# interstage_A2v2.net
KiCad netlist of a schematic drawn in EAGLE
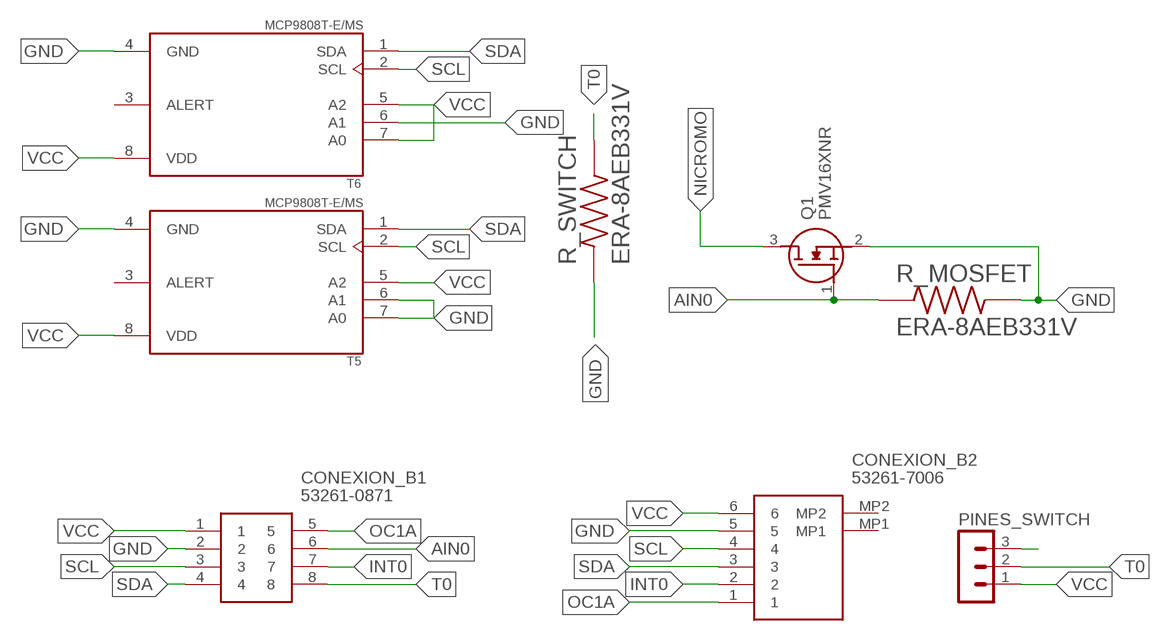
[diagram p0: schematic, sheet 1]

(export (version "E")
  (design (tool "Eeschema 10.0.6"))
  (components
    (comp (ref "CONEXION_B1")
      (value "53261-0871")
      (footprint "eagle-import:53261-0871")
      (fields (field (name "MOUSER_PART_NUMBER") "538-53261-0871"))
      (libsource (lib "eagle-import") (part "53261-0871"))
    )
    (comp (ref "CONEXION_B2")
      (value "53261-7006")
      (footprint "eagle-import:532617006")
      (fields (field (name "MOUSER_PART_NUMBER") "538-53261-7006"))
      (libsource (lib "eagle-import") (part "53261-7006"))
    )
    (comp (ref "PINES_SWITCH")
      (value "MA03-1")
      (footprint "eagle-import:MA03-1")
      (libsource (lib "eagle-import") (part "MA03-1"))
    )
    (comp (ref "Q1")
      (value "PMV16XNR")
      (footprint "eagle-import:SOT95P230X110-3N")
      (fields (field (name "MOUSER_PART_NUMBER") "771-PMV16XNR"))
      (libsource (lib "eagle-import") (part "PMV16XNR"))
    )
    (comp (ref "R_MOSFET")
      (value "ERA-8AEB331V")
      (footprint "eagle-import:RESC3216X70N")
      (fields (field (name "DIGI-KEY_PART_NUMBER") "P330BCCT-ND") (field (name "MF") "Panasonic Electronic"))
      (libsource (lib "eagle-import") (part "ERA-8AEB331V"))
    )
    (comp (ref "R_SWITCH")
      (value "ERA-8AEB331V")
      (footprint "eagle-import:RESC3216X70N")
      (fields (field (name "DIGI-KEY_PART_NUMBER") "P330BCCT-ND") (field (name "MF") "Panasonic Electronic"))
      (libsource (lib "eagle-import") (part "ERA-8AEB331V"))
    )
    (comp (ref "T5")
      (value "MCP9808T-E/MS")
      (footprint "eagle-import:SOP65P490X110-8N")
      (fields (field (name "DIGI-KEY_PART_NUMBER") "MCP9808T-E/MSCT-ND") (field (name "MF") "Microchip"))
      (libsource (lib "eagle-import") (part "MCP9808T-E/MS"))
    )
    (comp (ref "T6")
      (value "MCP9808T-E/MS")
      (footprint "eagle-import:SOP65P490X110-8N")
      (fields (field (name "DIGI-KEY_PART_NUMBER") "MCP9808T-E/MSCT-ND") (field (name "MF") "Microchip"))
      (libsource (lib "eagle-import") (part "MCP9808T-E/MS"))
    )
  )
  (nets
    (net (code "1") (name "AIN0") (class "Default")
      (node (ref "CONEXION_B1") (pin "6") (pinfunction "6_6") (pintype "bidirectional"))
      (node (ref "Q1") (pin "1") (pinfunction "G_1") (pintype "bidirectional"))
      (node (ref "R_MOSFET") (pin "1") (pinfunction "1_1") (pintype "passive"))
    )
    (net (code "2") (name "GND") (class "Default")
      (node (ref "CONEXION_B1") (pin "2") (pinfunction "2_2") (pintype "bidirectional"))
      (node (ref "CONEXION_B2") (pin "5") (pinfunction "5_5") (pintype "bidirectional"))
      (node (ref "Q1") (pin "2") (pinfunction "S_2") (pintype "bidirectional"))
      (node (ref "R_MOSFET") (pin "2") (pinfunction "2_2") (pintype "passive"))
      (node (ref "R_SWITCH") (pin "1") (pinfunction "1_1") (pintype "passive"))
      (node (ref "T5") (pin "4") (pinfunction "GND_4") (pintype "power_in"))
      (node (ref "T5") (pin "6") (pinfunction "A1_6") (pintype "input"))
      (node (ref "T5") (pin "7") (pinfunction "A0_7") (pintype "input"))
      (node (ref "T6") (pin "4") (pinfunction "GND_4") (pintype "power_in"))
      (node (ref "T6") (pin "6") (pinfunction "A1_6") (pintype "input"))
    )
    (net (code "3") (name "INT0") (class "Default")
      (node (ref "CONEXION_B1") (pin "7") (pinfunction "7_7") (pintype "bidirectional"))
      (node (ref "CONEXION_B2") (pin "2") (pinfunction "2_2") (pintype "bidirectional"))
    )
    (net (code "4") (name "NICROMO") (class "Default")
      (node (ref "Q1") (pin "3") (pinfunction "D_3") (pintype "bidirectional"))
    )
    (net (code "5") (name "OC1A") (class "Default")
      (node (ref "CONEXION_B1") (pin "5") (pinfunction "5_5") (pintype "bidirectional"))
      (node (ref "CONEXION_B2") (pin "1") (pinfunction "1_1") (pintype "bidirectional"))
    )
    (net (code "6") (name "SCL") (class "Default")
      (node (ref "CONEXION_B1") (pin "3") (pinfunction "3_3") (pintype "bidirectional"))
      (node (ref "CONEXION_B2") (pin "4") (pinfunction "4_4") (pintype "bidirectional"))
      (node (ref "T5") (pin "2") (pinfunction "SCL_2") (pintype "input"))
      (node (ref "T6") (pin "2") (pinfunction "SCL_2") (pintype "input"))
    )
    (net (code "7") (name "SDA") (class "Default")
      (node (ref "CONEXION_B1") (pin "4") (pinfunction "4_4") (pintype "bidirectional"))
      (node (ref "CONEXION_B2") (pin "3") (pinfunction "3_3") (pintype "bidirectional"))
      (node (ref "T5") (pin "1") (pinfunction "SDA_1") (pintype "bidirectional"))
      (node (ref "T6") (pin "1") (pinfunction "SDA_1") (pintype "bidirectional"))
    )
    (net (code "8") (name "T0") (class "Default")
      (node (ref "CONEXION_B1") (pin "8") (pinfunction "8_8") (pintype "bidirectional"))
      (node (ref "PINES_SWITCH") (pin "2") (pinfunction "2_2") (pintype "passive"))
      (node (ref "R_SWITCH") (pin "2") (pinfunction "2_2") (pintype "passive"))
    )
    (net (code "9") (name "VCC") (class "Default")
      (node (ref "CONEXION_B1") (pin "1") (pinfunction "1_1") (pintype "bidirectional"))
      (node (ref "CONEXION_B2") (pin "6") (pinfunction "6_6") (pintype "bidirectional"))
      (node (ref "PINES_SWITCH") (pin "1") (pinfunction "1_1") (pintype "passive"))
      (node (ref "T5") (pin "5") (pinfunction "A2_5") (pintype "input"))
      (node (ref "T5") (pin "8") (pinfunction "VDD_8") (pintype "power_in"))
      (node (ref "T6") (pin "5") (pinfunction "A2_5") (pintype "input"))
      (node (ref "T6") (pin "7") (pinfunction "A0_7") (pintype "input"))
      (node (ref "T6") (pin "8") (pinfunction "VDD_8") (pintype "power_in"))
    )
    (net (code "10") (name "unconnected-(CONEXION_B2-PadMP1)") (class "Default")
      (node (ref "CONEXION_B2") (pin "MP1") (pinfunction "MP1_MP1") (pintype "bidirectional"))
    )
    (net (code "11") (name "unconnected-(CONEXION_B2-PadMP2)") (class "Default")
      (node (ref "CONEXION_B2") (pin "MP2") (pinfunction "MP2_MP2") (pintype "bidirectional"))
    )
    (net (code "12") (name "unconnected-(PINES_SWITCH-Pad3)") (class "Default")
      (node (ref "PINES_SWITCH") (pin "3") (pinfunction "3_3") (pintype "passive"))
    )
    (net (code "13") (name "unconnected-(T5-ALERT-Pad3)") (class "Default")
      (node (ref "T5") (pin "3") (pinfunction "ALERT_3") (pintype "output"))
    )
    (net (code "14") (name "unconnected-(T6-ALERT-Pad3)") (class "Default")
      (node (ref "T6") (pin "3") (pinfunction "ALERT_3") (pintype "output"))
    )
  )
)
